# Connectors.net
KiCad netlist of a schematic drawn in Altium Designer
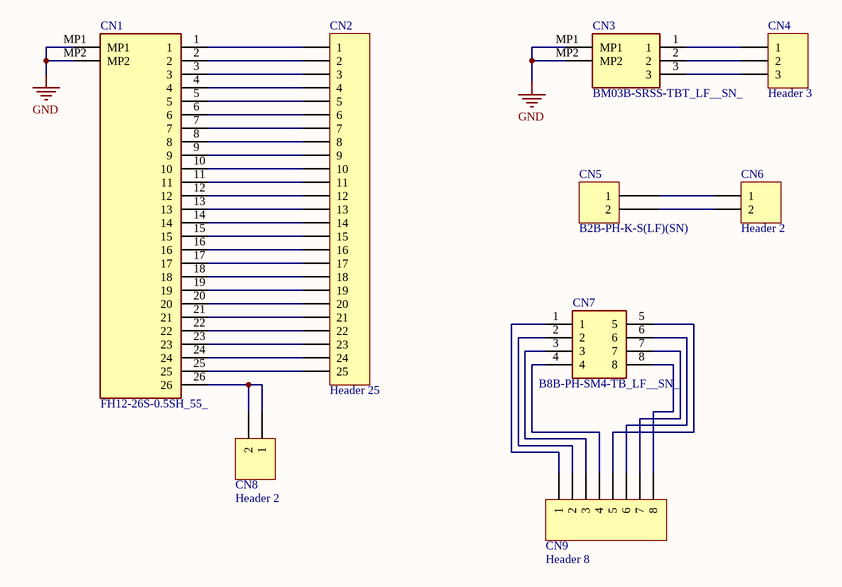
[diagram p0: Connectors.SchDoc]

(export (version "E")
  (design (tool "Eeschema 10.0.6"))
  (components
    (comp (ref "CN1")
      (value "FH12-26S-0.5SH_55_")
      (footprint "SamacSys:FH1226S05SH55")
      (description "Connector")
      (fields
        (field (name "MANUFACTURER_PART_NUMBER") "FH12-26S-0.5SH(55)")
        (field (name "MOUSER PART NUMBER") "798-FH12-26S-0.5SH55")
      )
      (libsource (lib "SamacSys") (part "FH12-26S-0.5SH_55_"))
    )
    (comp (ref "CN2")
      (value "Header 25")
      (footprint "HDR1X25")
      (description "Header, 25-Pin")
      (fields (field (name "PUBLISHER") "Altium Limited"))
      (libsource (lib "Miscellaneous Connectors") (part "Header 25"))
    )
    (comp (ref "CN3")
      (value "BM03B-SRSS-TBT_LF__SN_")
      (footprint "SamacSys:BM03BSRSSTBTLFSN")
      (description "Connector")
      (fields (field (name "MANUFACTURER_PART_NUMBER") "BM03B-SRSS-TBT(LF)(SN)"))
      (libsource (lib "*") (part "BM03B-SRSS-TBT_LF__SN_"))
    )
    (comp (ref "CN4")
      (value "Header 3")
      (footprint "HDR1X3")
      (description "Header, 3-Pin")
      (fields (field (name "PUBLISHER") "Altium Limited"))
      (libsource (lib "Miscellaneous Connectors") (part "Header 3"))
    )
    (comp (ref "CN5")
      (value "B2B-PH-K-S(LF)(SN)")
      (footprint "JST B2B-PH-K")
      (description "CONN HEADER VERT 2POS 2MM")
      (fields (field (name "MANUFACTURER") "JST Sales America Inc."))
      (libsource (lib "Celestial Altium Library - altium_library") (part "2 Pin"))
    )
    (comp (ref "CN6")
      (value "Header 2")
      (footprint "HDR1X2")
      (description "Header, 2-Pin")
      (fields (field (name "PUBLISHER") "Altium Limited"))
      (libsource (lib "") (part "Header 2_1"))
    )
    (comp (ref "CN7")
      (value "B8B-PH-SM4-TB_LF__SN_")
      (footprint "SamacSys:B8B-PH-SM4-TB")
      (description "Connector")
      (fields (field (name "MANUFACTURER_PART_NUMBER") "B8B-PH-SM4-TB(LF)(SN)"))
      (libsource (lib "*") (part "B8B-PH-SM4-TB_LF__SN_"))
    )
    (comp (ref "CN8")
      (value "Header 2")
      (footprint "HDR1X2")
      (description "Header, 2-Pin")
      (fields (field (name "PUBLISHER") "Altium Limited"))
      (libsource (lib "Miscellaneous Connectors") (part "Header 2"))
    )
    (comp (ref "CN9")
      (value "Header 8")
      (footprint "HDR1X8")
      (description "Header, 8-Pin")
      (fields (field (name "PUBLISHER") "Altium Limited"))
      (libsource (lib "Miscellaneous Connectors") (part "Header 8"))
    )
  )
  (nets
    (net (code "1") (name "GND") (class "Default")
      (node (ref "CN1") (pin "MP1") (pinfunction "MP1_MP1") (pintype "passive"))
      (node (ref "CN1") (pin "MP2") (pinfunction "MP2_MP2") (pintype "passive"))
      (node (ref "CN3") (pin "MP1") (pinfunction "MP1_MP1") (pintype "passive"))
      (node (ref "CN3") (pin "MP2") (pinfunction "MP2_MP2") (pintype "passive"))
    )
    (net (code "2") (name "Net-(CN1-Pad1)") (class "Default")
      (node (ref "CN1") (pin "1") (pinfunction "1_1") (pintype "passive"))
      (node (ref "CN2") (pin "1") (pinfunction "1_1") (pintype "passive"))
    )
    (net (code "3") (name "Net-(CN1-Pad2)") (class "Default")
      (node (ref "CN1") (pin "2") (pinfunction "2_2") (pintype "passive"))
      (node (ref "CN2") (pin "2") (pinfunction "2_2") (pintype "passive"))
    )
    (net (code "4") (name "Net-(CN1-Pad3)") (class "Default")
      (node (ref "CN1") (pin "3") (pinfunction "3_3") (pintype "passive"))
      (node (ref "CN2") (pin "3") (pinfunction "3_3") (pintype "passive"))
    )
    (net (code "5") (name "Net-(CN1-Pad4)") (class "Default")
      (node (ref "CN1") (pin "4") (pinfunction "4_4") (pintype "passive"))
      (node (ref "CN2") (pin "4") (pinfunction "4_4") (pintype "passive"))
    )
    (net (code "6") (name "Net-(CN1-Pad5)") (class "Default")
      (node (ref "CN1") (pin "5") (pinfunction "5_5") (pintype "passive"))
      (node (ref "CN2") (pin "5") (pinfunction "5_5") (pintype "passive"))
    )
    (net (code "7") (name "Net-(CN1-Pad6)") (class "Default")
      (node (ref "CN1") (pin "6") (pinfunction "6_6") (pintype "passive"))
      (node (ref "CN2") (pin "6") (pinfunction "6_6") (pintype "passive"))
    )
    (net (code "8") (name "Net-(CN1-Pad7)") (class "Default")
      (node (ref "CN1") (pin "7") (pinfunction "7_7") (pintype "passive"))
      (node (ref "CN2") (pin "7") (pinfunction "7_7") (pintype "passive"))
    )
    (net (code "9") (name "Net-(CN1-Pad8)") (class "Default")
      (node (ref "CN1") (pin "8") (pinfunction "8_8") (pintype "passive"))
      (node (ref "CN2") (pin "8") (pinfunction "8_8") (pintype "passive"))
    )
    (net (code "10") (name "Net-(CN1-Pad9)") (class "Default")
      (node (ref "CN1") (pin "9") (pinfunction "9_9") (pintype "passive"))
      (node (ref "CN2") (pin "9") (pinfunction "9_9") (pintype "passive"))
    )
    (net (code "11") (name "Net-(CN1-Pad10)") (class "Default")
      (node (ref "CN1") (pin "10") (pinfunction "10_10") (pintype "passive"))
      (node (ref "CN2") (pin "10") (pinfunction "10_10") (pintype "passive"))
    )
    (net (code "12") (name "Net-(CN1-Pad11)") (class "Default")
      (node (ref "CN1") (pin "11") (pinfunction "11_11") (pintype "passive"))
      (node (ref "CN2") (pin "11") (pinfunction "11_11") (pintype "passive"))
    )
    (net (code "13") (name "Net-(CN1-Pad12)") (class "Default")
      (node (ref "CN1") (pin "12") (pinfunction "12_12") (pintype "passive"))
      (node (ref "CN2") (pin "12") (pinfunction "12_12") (pintype "passive"))
    )
    (net (code "14") (name "Net-(CN1-Pad13)") (class "Default")
      (node (ref "CN1") (pin "13") (pinfunction "13_13") (pintype "passive"))
      (node (ref "CN2") (pin "13") (pinfunction "13_13") (pintype "passive"))
    )
    (net (code "15") (name "Net-(CN1-Pad14)") (class "Default")
      (node (ref "CN1") (pin "14") (pinfunction "14_14") (pintype "passive"))
      (node (ref "CN2") (pin "14") (pinfunction "14_14") (pintype "passive"))
    )
    (net (code "16") (name "Net-(CN1-Pad15)") (class "Default")
      (node (ref "CN1") (pin "15") (pinfunction "15_15") (pintype "passive"))
      (node (ref "CN2") (pin "15") (pinfunction "15_15") (pintype "passive"))
    )
    (net (code "17") (name "Net-(CN1-Pad16)") (class "Default")
      (node (ref "CN1") (pin "16") (pinfunction "16_16") (pintype "passive"))
      (node (ref "CN2") (pin "16") (pinfunction "16_16") (pintype "passive"))
    )
    (net (code "18") (name "Net-(CN1-Pad17)") (class "Default")
      (node (ref "CN1") (pin "17") (pinfunction "17_17") (pintype "passive"))
      (node (ref "CN2") (pin "17") (pinfunction "17_17") (pintype "passive"))
    )
    (net (code "19") (name "Net-(CN1-Pad18)") (class "Default")
      (node (ref "CN1") (pin "18") (pinfunction "18_18") (pintype "passive"))
      (node (ref "CN2") (pin "18") (pinfunction "18_18") (pintype "passive"))
    )
    (net (code "20") (name "Net-(CN1-Pad19)") (class "Default")
      (node (ref "CN1") (pin "19") (pinfunction "19_19") (pintype "passive"))
      (node (ref "CN2") (pin "19") (pinfunction "19_19") (pintype "passive"))
    )
    (net (code "21") (name "Net-(CN1-Pad20)") (class "Default")
      (node (ref "CN1") (pin "20") (pinfunction "20_20") (pintype "passive"))
      (node (ref "CN2") (pin "20") (pinfunction "20_20") (pintype "passive"))
    )
    (net (code "22") (name "Net-(CN1-Pad21)") (class "Default")
      (node (ref "CN1") (pin "21") (pinfunction "21_21") (pintype "passive"))
      (node (ref "CN2") (pin "21") (pinfunction "21_21") (pintype "passive"))
    )
    (net (code "23") (name "Net-(CN1-Pad22)") (class "Default")
      (node (ref "CN1") (pin "22") (pinfunction "22_22") (pintype "passive"))
      (node (ref "CN2") (pin "22") (pinfunction "22_22") (pintype "passive"))
    )
    (net (code "24") (name "Net-(CN1-Pad23)") (class "Default")
      (node (ref "CN1") (pin "23") (pinfunction "23_23") (pintype "passive"))
      (node (ref "CN2") (pin "23") (pinfunction "23_23") (pintype "passive"))
    )
    (net (code "25") (name "Net-(CN1-Pad24)") (class "Default")
      (node (ref "CN1") (pin "24") (pinfunction "24_24") (pintype "passive"))
      (node (ref "CN2") (pin "24") (pinfunction "24_24") (pintype "passive"))
    )
    (net (code "26") (name "Net-(CN1-Pad25)") (class "Default")
      (node (ref "CN1") (pin "25") (pinfunction "25_25") (pintype "passive"))
      (node (ref "CN2") (pin "25") (pinfunction "25_25") (pintype "passive"))
    )
    (net (code "27") (name "Net-(CN1-Pad26)") (class "Default")
      (node (ref "CN1") (pin "26") (pinfunction "26_26") (pintype "passive"))
      (node (ref "CN8") (pin "1") (pinfunction "1_1") (pintype "passive"))
      (node (ref "CN8") (pin "2") (pinfunction "2_2") (pintype "passive"))
    )
    (net (code "28") (name "Net-(CN3-Pad1)") (class "Default")
      (node (ref "CN3") (pin "1") (pinfunction "1_1") (pintype "passive"))
      (node (ref "CN4") (pin "1") (pinfunction "1_1") (pintype "passive"))
    )
    (net (code "29") (name "Net-(CN3-Pad2)") (class "Default")
      (node (ref "CN3") (pin "2") (pinfunction "2_2") (pintype "passive"))
      (node (ref "CN4") (pin "2") (pinfunction "2_2") (pintype "passive"))
    )
    (net (code "30") (name "Net-(CN3-Pad3)") (class "Default")
      (node (ref "CN3") (pin "3") (pinfunction "3_3") (pintype "passive"))
      (node (ref "CN4") (pin "3") (pinfunction "3_3") (pintype "passive"))
    )
    (net (code "31") (name "Net-(CN5-Pad1)") (class "Default")
      (node (ref "CN5") (pin "1") (pinfunction "1_1") (pintype "passive"))
      (node (ref "CN6") (pin "1") (pinfunction "1_1") (pintype "passive"))
    )
    (net (code "32") (name "Net-(CN5-Pad2)") (class "Default")
      (node (ref "CN5") (pin "2") (pinfunction "2_2") (pintype "passive"))
      (node (ref "CN6") (pin "2") (pinfunction "2_2") (pintype "passive"))
    )
    (net (code "33") (name "Net-(CN7-Pad1)") (class "Default")
      (node (ref "CN7") (pin "1") (pinfunction "1_1") (pintype "passive"))
      (node (ref "CN9") (pin "1") (pinfunction "1_1") (pintype "passive"))
    )
    (net (code "34") (name "Net-(CN7-Pad2)") (class "Default")
      (node (ref "CN7") (pin "2") (pinfunction "2_2") (pintype "passive"))
      (node (ref "CN9") (pin "2") (pinfunction "2_2") (pintype "passive"))
    )
    (net (code "35") (name "Net-(CN7-Pad3)") (class "Default")
      (node (ref "CN7") (pin "3") (pinfunction "3_3") (pintype "passive"))
      (node (ref "CN9") (pin "3") (pinfunction "3_3") (pintype "passive"))
    )
    (net (code "36") (name "Net-(CN7-Pad4)") (class "Default")
      (node (ref "CN7") (pin "4") (pinfunction "4_4") (pintype "passive"))
      (node (ref "CN9") (pin "4") (pinfunction "4_4") (pintype "passive"))
    )
    (net (code "37") (name "Net-(CN7-Pad5)") (class "Default")
      (node (ref "CN7") (pin "5") (pinfunction "5_5") (pintype "passive"))
      (node (ref "CN9") (pin "5") (pinfunction "5_5") (pintype "passive"))
    )
    (net (code "38") (name "Net-(CN7-Pad6)") (class "Default")
      (node (ref "CN7") (pin "6") (pinfunction "6_6") (pintype "passive"))
      (node (ref "CN9") (pin "6") (pinfunction "6_6") (pintype "passive"))
    )
    (net (code "39") (name "Net-(CN7-Pad7)") (class "Default")
      (node (ref "CN7") (pin "7") (pinfunction "7_7") (pintype "passive"))
      (node (ref "CN9") (pin "7") (pinfunction "7_7") (pintype "passive"))
    )
    (net (code "40") (name "Net-(CN7-Pad8)") (class "Default")
      (node (ref "CN7") (pin "8") (pinfunction "8_8") (pintype "passive"))
      (node (ref "CN9") (pin "8") (pinfunction "8_8") (pintype "passive"))
    )
  )
)
